# rs232.net
KiCad netlist of a schematic drawn in EAGLE
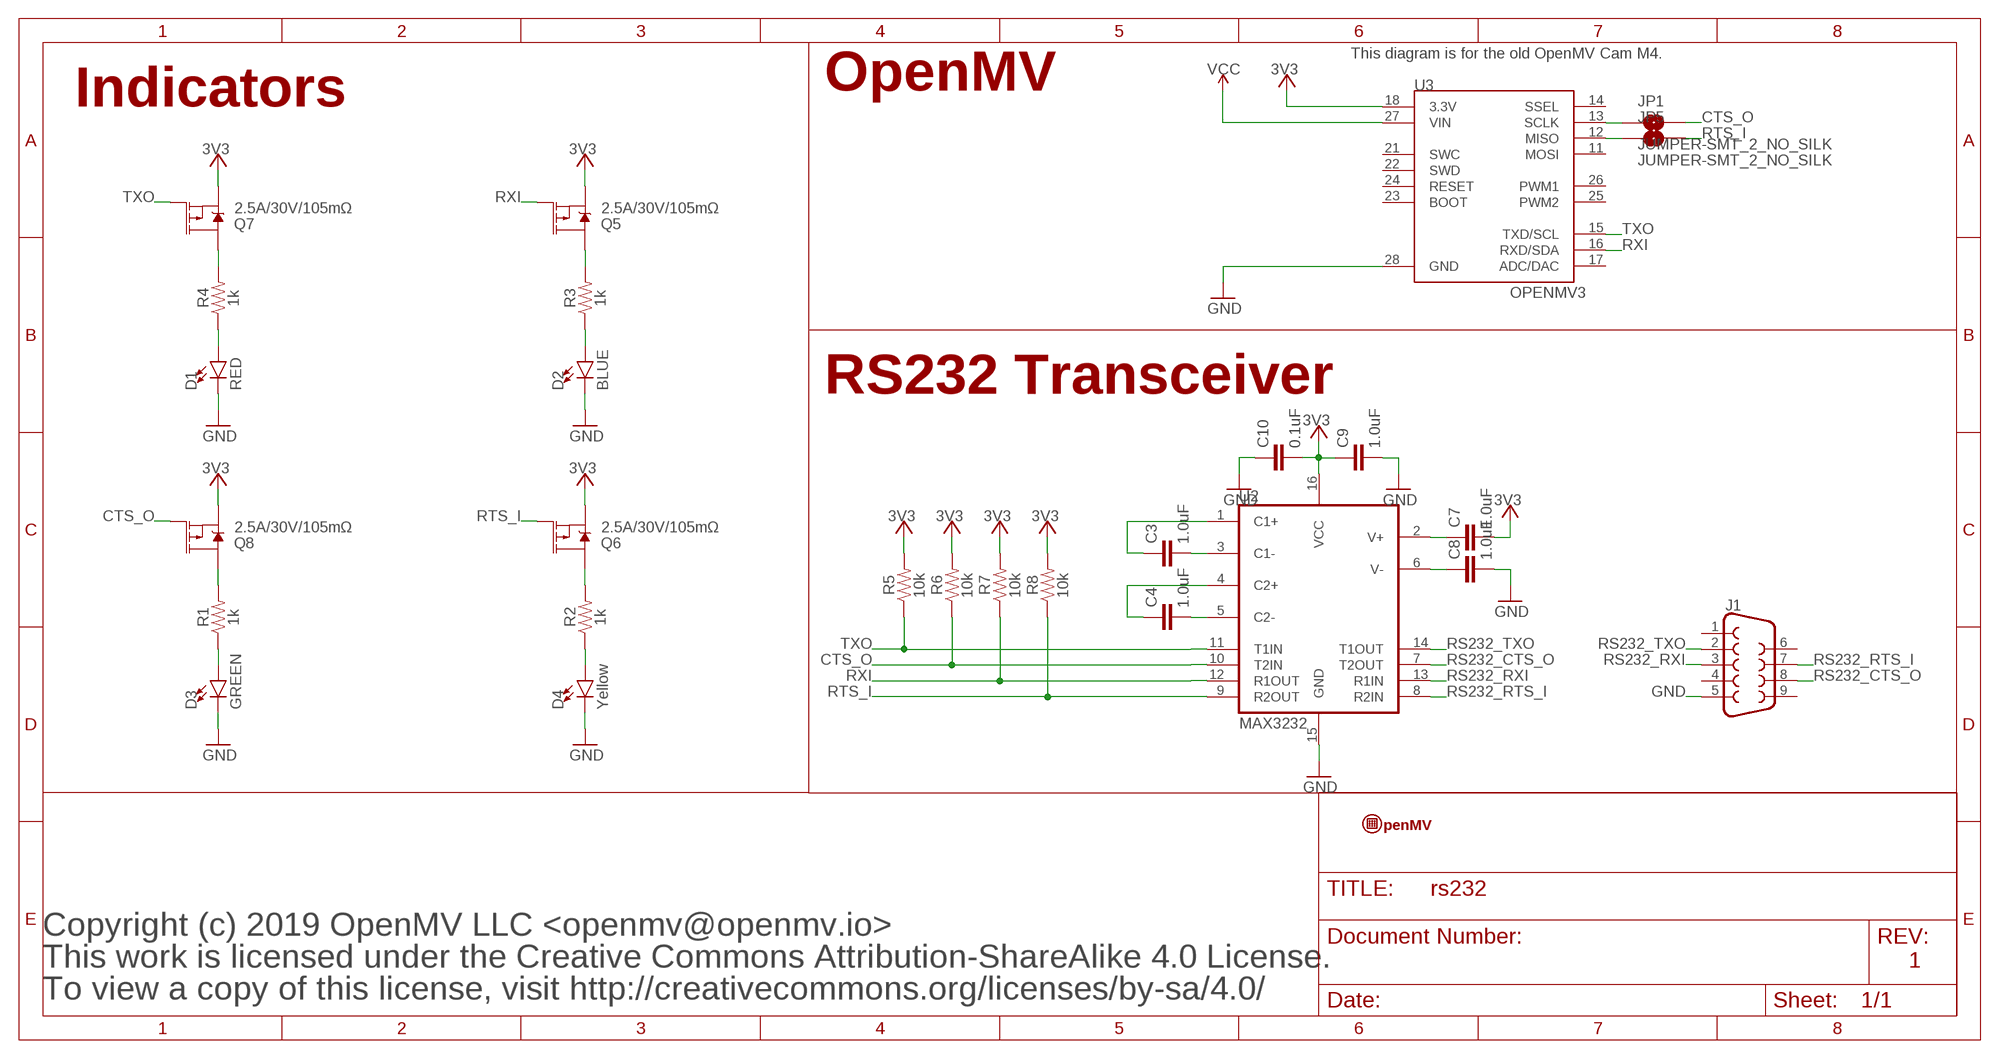
[diagram p0: schematic, sheet 1]

(export (version "E")
  (design (tool "Eeschema 10.0.6"))
  (components
    (comp (ref "C3")
      (value "1.0uF")
      (footprint "eagle-import:0603")
      (libsource (lib "eagle-import") (part "1.0UF-0603-16V-10%"))
    )
    (comp (ref "C4")
      (value "1.0uF")
      (footprint "eagle-import:0603")
      (libsource (lib "eagle-import") (part "1.0UF-0603-16V-10%"))
    )
    (comp (ref "C7")
      (value "1.0uF")
      (footprint "eagle-import:0603")
      (libsource (lib "eagle-import") (part "1.0UF-0603-16V-10%"))
    )
    (comp (ref "C8")
      (value "1.0uF")
      (footprint "eagle-import:0603")
      (libsource (lib "eagle-import") (part "1.0UF-0603-16V-10%"))
    )
    (comp (ref "C9")
      (value "1.0uF")
      (footprint "eagle-import:0603")
      (libsource (lib "eagle-import") (part "1.0UF-0603-16V-10%"))
    )
    (comp (ref "C10")
      (value "0.1uF")
      (footprint "eagle-import:0603")
      (libsource (lib "eagle-import") (part "0.1UF-0603-25V-(+80/-20%)"))
    )
    (comp (ref "D1")
      (value "RED")
      (footprint "eagle-import:LED-0603")
      (libsource (lib "eagle-import") (part "LED-RED0603"))
    )
    (comp (ref "D2")
      (value "BLUE")
      (footprint "eagle-import:LED-0603")
      (libsource (lib "eagle-import") (part "LED-BLUE0603"))
    )
    (comp (ref "D3")
      (value "GREEN")
      (footprint "eagle-import:LED-0603")
      (libsource (lib "eagle-import") (part "LED-GREEN0603"))
    )
    (comp (ref "D4")
      (value "Yellow")
      (footprint "eagle-import:LED-0603")
      (libsource (lib "eagle-import") (part "LED-YELLOW0603"))
    )
    (comp (ref "J1")
      (value "DB9FEMALE")
      (footprint "eagle-import:DB9")
      (libsource (lib "eagle-import") (part "DB9FEMALE"))
    )
    (comp (ref "JP1")
      (value "JUMPER-SMT_2_NO_SILK")
      (footprint "eagle-import:SMT-JUMPER_2_NO_SILK")
      (libsource (lib "eagle-import") (part "JUMPER-SMT_2_NO_SILK"))
    )
    (comp (ref "JP5")
      (value "JUMPER-SMT_2_NO_SILK")
      (footprint "eagle-import:SMT-JUMPER_2_NO_SILK")
      (libsource (lib "eagle-import") (part "JUMPER-SMT_2_NO_SILK"))
    )
    (comp (ref "Q5")
      (value "2.5A/30V/105mΩ")
      (footprint "eagle-import:SOT23-3")
      (libsource (lib "eagle-import") (part "MOSFET_PCH-DMG2307L"))
    )
    (comp (ref "Q6")
      (value "2.5A/30V/105mΩ")
      (footprint "eagle-import:SOT23-3")
      (libsource (lib "eagle-import") (part "MOSFET_PCH-DMG2307L"))
    )
    (comp (ref "Q7")
      (value "2.5A/30V/105mΩ")
      (footprint "eagle-import:SOT23-3")
      (libsource (lib "eagle-import") (part "MOSFET_PCH-DMG2307L"))
    )
    (comp (ref "Q8")
      (value "2.5A/30V/105mΩ")
      (footprint "eagle-import:SOT23-3")
      (libsource (lib "eagle-import") (part "MOSFET_PCH-DMG2307L"))
    )
    (comp (ref "R1")
      (value "1k")
      (footprint "eagle-import:0603")
      (libsource (lib "eagle-import") (part "1KOHM-0603-1/10W-1%"))
    )
    (comp (ref "R2")
      (value "1k")
      (footprint "eagle-import:0603")
      (libsource (lib "eagle-import") (part "1KOHM-0603-1/10W-1%"))
    )
    (comp (ref "R3")
      (value "1k")
      (footprint "eagle-import:0603")
      (libsource (lib "eagle-import") (part "1KOHM-0603-1/10W-1%"))
    )
    (comp (ref "R4")
      (value "1k")
      (footprint "eagle-import:0603")
      (libsource (lib "eagle-import") (part "1KOHM-0603-1/10W-1%"))
    )
    (comp (ref "R5")
      (value "10k")
      (footprint "eagle-import:0603")
      (libsource (lib "eagle-import") (part "10KOHM-0603-1/10W-1%"))
    )
    (comp (ref "R6")
      (value "10k")
      (footprint "eagle-import:0603")
      (libsource (lib "eagle-import") (part "10KOHM-0603-1/10W-1%"))
    )
    (comp (ref "R7")
      (value "10k")
      (footprint "eagle-import:0603")
      (libsource (lib "eagle-import") (part "10KOHM-0603-1/10W-1%"))
    )
    (comp (ref "R8")
      (value "10k")
      (footprint "eagle-import:0603")
      (libsource (lib "eagle-import") (part "10KOHM-0603-1/10W-1%"))
    )
    (comp (ref "U$9")
      (value "OPENMV-LOGO")
      (footprint "eagle-import:OPENMV-LOGO")
      (libsource (lib "eagle-import") (part "OPENMV-LOGO"))
    )
    (comp (ref "U2")
      (value "MAX3232")
      (footprint "eagle-import:SO16")
      (libsource (lib "eagle-import") (part "MAX2323SOIC16"))
    )
    (comp (ref "U3")
      (value "OPENMV3")
      (footprint "eagle-import:OPENMV3")
      (libsource (lib "eagle-import") (part "OPENMV3"))
    )
  )
  (nets
    (net (code "1") (name "/CTS_O") (class "Default")
      (node (ref "JP1") (pin "2") (pinfunction "2_2") (pintype "passive"))
      (node (ref "Q8") (pin "1") (pinfunction "G_1") (pintype "bidirectional"))
      (node (ref "R6") (pin "1") (pinfunction "1_1") (pintype "passive"))
      (node (ref "U2") (pin "10") (pinfunction "T2IN_10") (pintype "input"))
    )
    (net (code "2") (name "/RS232_CTS_O") (class "Default")
      (node (ref "J1") (pin "8") (pinfunction "8_8") (pintype "passive"))
      (node (ref "U2") (pin "7") (pinfunction "T2OUT_7") (pintype "output"))
    )
    (net (code "3") (name "/RS232_RTS_I") (class "Default")
      (node (ref "J1") (pin "7") (pinfunction "7_7") (pintype "passive"))
      (node (ref "U2") (pin "8") (pinfunction "R2IN_8") (pintype "input"))
    )
    (net (code "4") (name "/RS232_RXI") (class "Default")
      (node (ref "J1") (pin "3") (pinfunction "3_3") (pintype "passive"))
      (node (ref "U2") (pin "13") (pinfunction "R1IN_13") (pintype "input"))
    )
    (net (code "5") (name "/RS232_TXO") (class "Default")
      (node (ref "J1") (pin "2") (pinfunction "2_2") (pintype "passive"))
      (node (ref "U2") (pin "14") (pinfunction "T1OUT_14") (pintype "output"))
    )
    (net (code "6") (name "/RTS_I") (class "Default")
      (node (ref "JP5") (pin "2") (pinfunction "2_2") (pintype "passive"))
      (node (ref "Q6") (pin "1") (pinfunction "G_1") (pintype "bidirectional"))
      (node (ref "R8") (pin "1") (pinfunction "1_1") (pintype "passive"))
      (node (ref "U2") (pin "9") (pinfunction "R2OUT_9") (pintype "output"))
    )
    (net (code "7") (name "/RXI") (class "Default")
      (node (ref "Q5") (pin "1") (pinfunction "G_1") (pintype "bidirectional"))
      (node (ref "R7") (pin "1") (pinfunction "1_1") (pintype "passive"))
      (node (ref "U2") (pin "12") (pinfunction "R1OUT_12") (pintype "output"))
      (node (ref "U3") (pin "16") (pinfunction "RXD/SDA_16") (pintype "bidirectional"))
    )
    (net (code "8") (name "/TXO") (class "Default")
      (node (ref "Q7") (pin "1") (pinfunction "G_1") (pintype "bidirectional"))
      (node (ref "R5") (pin "1") (pinfunction "1_1") (pintype "passive"))
      (node (ref "U2") (pin "11") (pinfunction "T1IN_11") (pintype "input"))
      (node (ref "U3") (pin "15") (pinfunction "TXD/SCL_15") (pintype "bidirectional"))
    )
    (net (code "9") (name "3V3") (class "Default")
      (node (ref "C10") (pin "2") (pinfunction "2_2") (pintype "passive"))
      (node (ref "C7") (pin "2") (pinfunction "2_2") (pintype "passive"))
      (node (ref "C9") (pin "1") (pinfunction "1_1") (pintype "passive"))
      (node (ref "Q5") (pin "2") (pinfunction "S_2") (pintype "bidirectional"))
      (node (ref "Q6") (pin "2") (pinfunction "S_2") (pintype "bidirectional"))
      (node (ref "Q7") (pin "2") (pinfunction "S_2") (pintype "bidirectional"))
      (node (ref "Q8") (pin "2") (pinfunction "S_2") (pintype "bidirectional"))
      (node (ref "R5") (pin "2") (pinfunction "2_2") (pintype "passive"))
      (node (ref "R6") (pin "2") (pinfunction "2_2") (pintype "passive"))
      (node (ref "R7") (pin "2") (pinfunction "2_2") (pintype "passive"))
      (node (ref "R8") (pin "2") (pinfunction "2_2") (pintype "passive"))
      (node (ref "U2") (pin "16") (pinfunction "VCC_16") (pintype "bidirectional"))
      (node (ref "U3") (pin "18") (pinfunction "3.3V_18") (pintype "power_in"))
    )
    (net (code "10") (name "GND") (class "Default")
      (node (ref "C10") (pin "1") (pinfunction "1_1") (pintype "passive"))
      (node (ref "C8") (pin "2") (pinfunction "2_2") (pintype "passive"))
      (node (ref "C9") (pin "2") (pinfunction "2_2") (pintype "passive"))
      (node (ref "D1") (pin "C") (pinfunction "C_C") (pintype "passive"))
      (node (ref "D2") (pin "C") (pinfunction "C_C") (pintype "passive"))
      (node (ref "D3") (pin "C") (pinfunction "C_C") (pintype "passive"))
      (node (ref "D4") (pin "C") (pinfunction "C_C") (pintype "passive"))
      (node (ref "J1") (pin "5") (pinfunction "5_5") (pintype "passive"))
      (node (ref "U2") (pin "15") (pinfunction "GND_15") (pintype "bidirectional"))
      (node (ref "U3") (pin "28") (pinfunction "GND_28") (pintype "power_in"))
    )
    (net (code "11") (name "Net-(D1-PadA)") (class "Default")
      (node (ref "D1") (pin "A") (pinfunction "A_A") (pintype "passive"))
      (node (ref "R4") (pin "1") (pinfunction "1_1") (pintype "passive"))
    )
    (net (code "12") (name "Net-(D2-PadA)") (class "Default")
      (node (ref "D2") (pin "A") (pinfunction "A_A") (pintype "passive"))
      (node (ref "R3") (pin "1") (pinfunction "1_1") (pintype "passive"))
    )
    (net (code "13") (name "Net-(D3-PadA)") (class "Default")
      (node (ref "D3") (pin "A") (pinfunction "A_A") (pintype "passive"))
      (node (ref "R1") (pin "1") (pinfunction "1_1") (pintype "passive"))
    )
    (net (code "14") (name "Net-(D4-PadA)") (class "Default")
      (node (ref "D4") (pin "A") (pinfunction "A_A") (pintype "passive"))
      (node (ref "R2") (pin "1") (pinfunction "1_1") (pintype "passive"))
    )
    (net (code "15") (name "Net-(Q5-D)") (class "Default")
      (node (ref "Q5") (pin "3") (pinfunction "D_3") (pintype "bidirectional"))
      (node (ref "R3") (pin "2") (pinfunction "2_2") (pintype "passive"))
    )
    (net (code "16") (name "Net-(Q6-D)") (class "Default")
      (node (ref "Q6") (pin "3") (pinfunction "D_3") (pintype "bidirectional"))
      (node (ref "R2") (pin "2") (pinfunction "2_2") (pintype "passive"))
    )
    (net (code "17") (name "Net-(Q7-D)") (class "Default")
      (node (ref "Q7") (pin "3") (pinfunction "D_3") (pintype "bidirectional"))
      (node (ref "R4") (pin "2") (pinfunction "2_2") (pintype "passive"))
    )
    (net (code "18") (name "Net-(Q8-D)") (class "Default")
      (node (ref "Q8") (pin "3") (pinfunction "D_3") (pintype "bidirectional"))
      (node (ref "R1") (pin "2") (pinfunction "2_2") (pintype "passive"))
    )
    (net (code "19") (name "Net-(U2-C1+)") (class "Default")
      (node (ref "C3") (pin "1") (pinfunction "1_1") (pintype "passive"))
      (node (ref "U2") (pin "1") (pinfunction "C1+_1") (pintype "bidirectional"))
    )
    (net (code "20") (name "Net-(U2-C1-)") (class "Default")
      (node (ref "C3") (pin "2") (pinfunction "2_2") (pintype "passive"))
      (node (ref "U2") (pin "3") (pinfunction "C1-_3") (pintype "bidirectional"))
    )
    (net (code "21") (name "Net-(U2-C2+)") (class "Default")
      (node (ref "C4") (pin "1") (pinfunction "1_1") (pintype "passive"))
      (node (ref "U2") (pin "4") (pinfunction "C2+_4") (pintype "bidirectional"))
    )
    (net (code "22") (name "Net-(U2-C2-)") (class "Default")
      (node (ref "C4") (pin "2") (pinfunction "2_2") (pintype "passive"))
      (node (ref "U2") (pin "5") (pinfunction "C2-_5") (pintype "bidirectional"))
    )
    (net (code "23") (name "Net-(U2-V+)") (class "Default")
      (node (ref "C7") (pin "1") (pinfunction "1_1") (pintype "passive"))
      (node (ref "U2") (pin "2") (pinfunction "V+_2") (pintype "bidirectional"))
    )
    (net (code "24") (name "Net-(U2-V-)") (class "Default")
      (node (ref "C8") (pin "1") (pinfunction "1_1") (pintype "passive"))
      (node (ref "U2") (pin "6") (pinfunction "V-_6") (pintype "bidirectional"))
    )
    (net (code "25") (name "Net-(U3-MISO)") (class "Default")
      (node (ref "JP5") (pin "1") (pinfunction "1_1") (pintype "passive"))
      (node (ref "U3") (pin "12") (pinfunction "MISO_12") (pintype "bidirectional"))
    )
    (net (code "26") (name "Net-(U3-SCLK)") (class "Default")
      (node (ref "JP1") (pin "1") (pinfunction "1_1") (pintype "passive"))
      (node (ref "U3") (pin "13") (pinfunction "SCLK_13") (pintype "bidirectional"))
    )
    (net (code "27") (name "VCC") (class "Default")
      (node (ref "U3") (pin "27") (pinfunction "VIN_27") (pintype "power_in"))
    )
    (net (code "28") (name "unconnected-(J1-Pad1)") (class "Default")
      (node (ref "J1") (pin "1") (pinfunction "1_1") (pintype "passive"))
    )
    (net (code "29") (name "unconnected-(J1-Pad4)") (class "Default")
      (node (ref "J1") (pin "4") (pinfunction "4_4") (pintype "passive"))
    )
    (net (code "30") (name "unconnected-(J1-Pad6)") (class "Default")
      (node (ref "J1") (pin "6") (pinfunction "6_6") (pintype "passive"))
    )
    (net (code "31") (name "unconnected-(J1-Pad9)") (class "Default")
      (node (ref "J1") (pin "9") (pinfunction "9_9") (pintype "passive"))
    )
    (net (code "32") (name "unconnected-(U3-ADC{slash}DAC-Pad17)") (class "Default")
      (node (ref "U3") (pin "17") (pinfunction "ADC/DAC_17") (pintype "bidirectional"))
    )
    (net (code "33") (name "unconnected-(U3-BOOT-Pad23)") (class "Default")
      (node (ref "U3") (pin "23") (pinfunction "BOOT_23") (pintype "bidirectional"))
    )
    (net (code "34") (name "unconnected-(U3-MOSI-Pad11)") (class "Default")
      (node (ref "U3") (pin "11") (pinfunction "MOSI_11") (pintype "bidirectional"))
    )
    (net (code "35") (name "unconnected-(U3-PWM1-Pad26)") (class "Default")
      (node (ref "U3") (pin "26") (pinfunction "PWM1_26") (pintype "bidirectional"))
    )
    (net (code "36") (name "unconnected-(U3-PWM2-Pad25)") (class "Default")
      (node (ref "U3") (pin "25") (pinfunction "PWM2_25") (pintype "bidirectional"))
    )
    (net (code "37") (name "unconnected-(U3-RESET-Pad24)") (class "Default")
      (node (ref "U3") (pin "24") (pinfunction "RESET_24") (pintype "bidirectional"))
    )
    (net (code "38") (name "unconnected-(U3-SSEL-Pad14)") (class "Default")
      (node (ref "U3") (pin "14") (pinfunction "SSEL_14") (pintype "bidirectional"))
    )
    (net (code "39") (name "unconnected-(U3-SWC-Pad21)") (class "Default")
      (node (ref "U3") (pin "21") (pinfunction "SWC_21") (pintype "bidirectional"))
    )
    (net (code "40") (name "unconnected-(U3-SWD-Pad22)") (class "Default")
      (node (ref "U3") (pin "22") (pinfunction "SWD_22") (pintype "bidirectional"))
    )
  )
)
